# Sensor_Board.net
KiCad netlist of a schematic drawn in Altium Designer
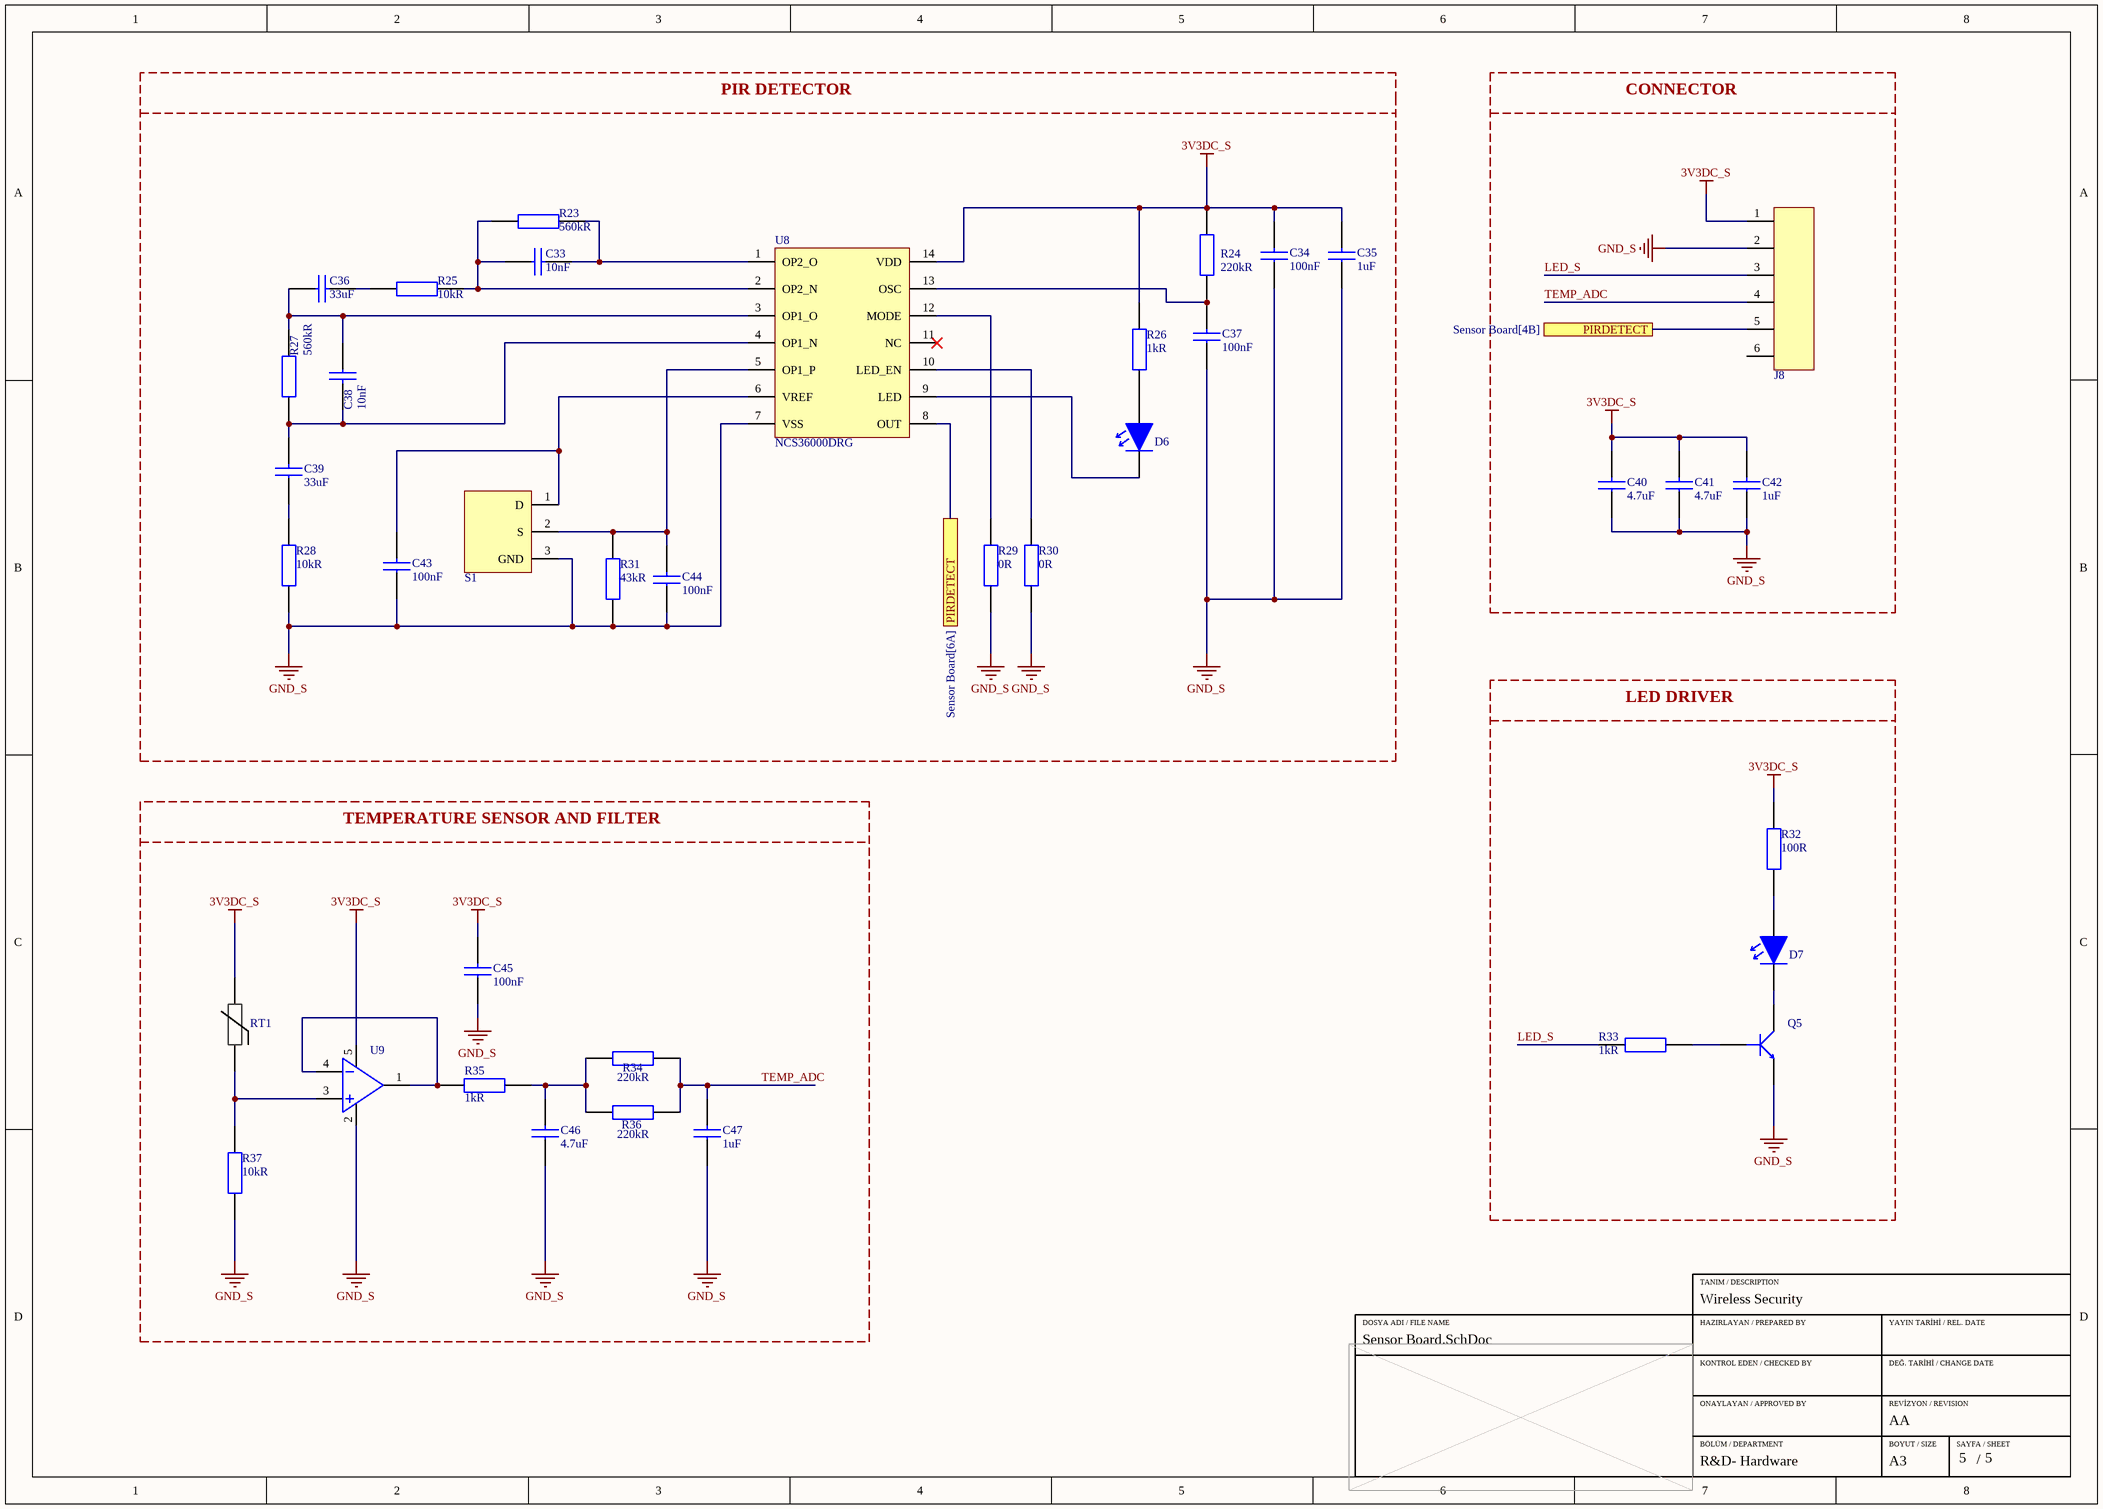
[diagram p0: Sensor Board.SchDoc]

(export (version "E")
  (design (tool "Eeschema 10.0.6"))
  (components
    (comp (ref "C33")
      (value "0603B103K160CT")
      (footprint "CAP_0603")
      (description "CAP CER 10nF %10 0603")
      (fields
        (field (name "MANUFACTURER") "Walsin Technologies")
        (field (name "TOLERANCE") "10%")
        (field (name "CAPACITANCE") "10nF")
        (field (name "DESIGNED BY") "Cem Uğurcan Özdemir")
      )
      (libsource (lib "UDEMY_Library") (part "CAP CER 10nF 0603"))
    )
    (comp (ref "C34")
      (value "C0603C104K5RACTU")
      (footprint "CAP_0603")
      (description "CAP CER 100nF %10 0603 SMD")
      (fields
        (field (name "MANUFACTURER") "KEMET")
        (field (name "TOLERANCE") "10%")
        (field (name "CAPACITANCE") "100nF")
        (field (name "DESIGNED BY") "Cem Uğurcan Özdemir")
      )
      (libsource (lib "UDEMY_Library") (part "CAP CER 100nF 0603"))
    )
    (comp (ref "C35")
      (value "CL21B105KBFNNNE")
      (footprint "CAP_0805")
      (description "CAP CER 1uF %10 0805")
      (fields
        (field (name "MANUFACTURER") "Samsung")
        (field (name "TOLERANCE") "10%")
        (field (name "CAPACITANCE") "1uF")
        (field (name "DESIGNED BY") "Cem Uğurcan Özdemir")
      )
      (libsource (lib "UDEMY_Library") (part "CAP CER 1uF 0805"))
    )
    (comp (ref "C36")
      (value "C3216X5R1E336M160AC")
      (footprint "CAP_1206")
      (description "CAP CER 33uF %20 1206 SMD")
      (fields
        (field (name "MANUFACTURER") "TDK")
        (field (name "TOLERANCE") "20%")
        (field (name "CAPACITANCE") "33uF")
        (field (name "DESIGNED BY") "Cem Uğurcan Özdemir")
      )
      (libsource (lib "UDEMY_Library") (part "CAP CER 33uF 1206"))
    )
    (comp (ref "C37")
      (value "C0603C104K5RACTU")
      (footprint "CAP_0603")
      (description "CAP CER 100nF %10 0603 SMD")
      (fields
        (field (name "MANUFACTURER") "KEMET")
        (field (name "TOLERANCE") "10%")
        (field (name "CAPACITANCE") "100nF")
        (field (name "DESIGNED BY") "Cem Uğurcan Özdemir")
      )
      (libsource (lib "UDEMY_Library") (part "CAP CER 100nF 0603"))
    )
    (comp (ref "C38")
      (value "0603B103K160CT")
      (footprint "CAP_0603")
      (description "CAP CER 10nF %10 0603")
      (fields
        (field (name "MANUFACTURER") "Walsin Technologies")
        (field (name "TOLERANCE") "10%")
        (field (name "CAPACITANCE") "10nF")
        (field (name "DESIGNED BY") "Cem Uğurcan Özdemir")
      )
      (libsource (lib "UDEMY_Library") (part "CAP CER 10nF 0603"))
    )
    (comp (ref "C39")
      (value "C3216X5R1E336M160AC")
      (footprint "CAP_1206")
      (description "CAP CER 33uF %20 1206 SMD")
      (fields
        (field (name "MANUFACTURER") "TDK")
        (field (name "TOLERANCE") "20%")
        (field (name "CAPACITANCE") "33uF")
        (field (name "DESIGNED BY") "Cem Uğurcan Özdemir")
      )
      (libsource (lib "UDEMY_Library") (part "CAP CER 33uF 1206"))
    )
    (comp (ref "C40")
      (value "CL21A475KAQNNNE")
      (footprint "CAP_0805")
      (description "CAP CER 4.7uF %10 0805")
      (fields
        (field (name "MANUFACTURER") "Samsung")
        (field (name "TOLERANCE") "10%")
        (field (name "CAPACITANCE") "4.7uF")
        (field (name "DESIGNED BY") "Cem Uğurcan Özdemir")
      )
      (libsource (lib "UDEMY_Library") (part "CAP CER 4.7uF 0805"))
    )
    (comp (ref "C41")
      (value "CL21A475KAQNNNE")
      (footprint "CAP_0805")
      (description "CAP CER 4.7uF %10 0805")
      (fields
        (field (name "MANUFACTURER") "Samsung")
        (field (name "TOLERANCE") "10%")
        (field (name "CAPACITANCE") "4.7uF")
        (field (name "DESIGNED BY") "Cem Uğurcan Özdemir")
      )
      (libsource (lib "UDEMY_Library") (part "CAP CER 4.7uF 0805"))
    )
    (comp (ref "C42")
      (value "CL21B105KBFNNNE")
      (footprint "CAP_0805")
      (description "CAP CER 1uF %10 0805")
      (fields
        (field (name "MANUFACTURER") "Samsung")
        (field (name "TOLERANCE") "10%")
        (field (name "CAPACITANCE") "1uF")
        (field (name "DESIGNED BY") "Cem Uğurcan Özdemir")
      )
      (libsource (lib "UDEMY_Library") (part "CAP CER 1uF 0805"))
    )
    (comp (ref "C43")
      (value "C0603C104K5RACTU")
      (footprint "CAP_0603")
      (description "CAP CER 100nF %10 0603 SMD")
      (fields
        (field (name "MANUFACTURER") "KEMET")
        (field (name "TOLERANCE") "10%")
        (field (name "CAPACITANCE") "100nF")
        (field (name "DESIGNED BY") "Cem Uğurcan Özdemir")
      )
      (libsource (lib "UDEMY_Library") (part "CAP CER 100nF 0603"))
    )
    (comp (ref "C44")
      (value "C0603C104K5RACTU")
      (footprint "CAP_0603")
      (description "CAP CER 100nF %10 0603 SMD")
      (fields
        (field (name "MANUFACTURER") "KEMET")
        (field (name "TOLERANCE") "10%")
        (field (name "CAPACITANCE") "100nF")
        (field (name "DESIGNED BY") "Cem Uğurcan Özdemir")
      )
      (libsource (lib "UDEMY_Library") (part "CAP CER 100nF 0603"))
    )
    (comp (ref "C45")
      (value "C0603C104K5RACTU")
      (footprint "CAP_0603")
      (description "CAP CER 100nF %10 0603 SMD")
      (fields
        (field (name "MANUFACTURER") "KEMET")
        (field (name "TOLERANCE") "10%")
        (field (name "CAPACITANCE") "100nF")
        (field (name "DESIGNED BY") "Cem Uğurcan Özdemir")
      )
      (libsource (lib "UDEMY_Library") (part "CAP CER 100nF 0603"))
    )
    (comp (ref "C46")
      (value "CL21A475KAQNNNE")
      (footprint "CAP_0805")
      (description "CAP CER 4.7uF %10 0805")
      (fields
        (field (name "MANUFACTURER") "Samsung")
        (field (name "TOLERANCE") "10%")
        (field (name "CAPACITANCE") "4.7uF")
        (field (name "DESIGNED BY") "Cem Uğurcan Özdemir")
      )
      (libsource (lib "UDEMY_Library") (part "CAP CER 4.7uF 0805"))
    )
    (comp (ref "C47")
      (value "CL21B105KBFNNNE")
      (footprint "CAP_0805")
      (description "CAP CER 1uF %10 0805")
      (fields
        (field (name "MANUFACTURER") "Samsung")
        (field (name "TOLERANCE") "10%")
        (field (name "CAPACITANCE") "1uF")
        (field (name "DESIGNED BY") "Cem Uğurcan Özdemir")
      )
      (libsource (lib "UDEMY_Library") (part "CAP CER 1uF 0805"))
    )
    (comp (ref "D6")
      (value "LTST-C171GKT")
      (footprint "LED_GREEN_0805")
      (description "Green 0805 130 º Min 5 mcd Typical 12 mcd Water Clear Lens SMT LED")
      (fields
        (field (name "MANUFACTURER") "Vishay Lite-On")
        (field (name "DESIGNED BY") "Cem Uğurcan Özdemir")
      )
      (libsource (lib "UDEMY_Library") (part "LED GREEN 0805"))
    )
    (comp (ref "D7")
      (value "LH R974-LP-1")
      (footprint "LED_RED_0805")
      (description "LED Uni-Color Hyper Red 660nm 2-Pin Chip 0805(2012Metric) T/R")
      (fields (field (name "MANUFACTURER") "Osram Opto") (field (name "DESIGNED BY") "Cem Uğurcan Özdemir"))
      (libsource (lib "UDEMY_Library") (part "LED RED 0805"))
    )
    (comp (ref "J8")
      (value "64800611622")
      (footprint "64800611622")
      (description "1.50mm 6PIN Connector")
      (fields
        (field (name "MANUFACTURER") "Wurth Electronics")
        (field (name "DESIGNED BY") "Cem Uğurcan Özdemir")
      )
      (libsource (lib "UDEMY_Library") (part "64800611622_conn_6pin"))
    )
    (comp (ref "Q5")
      (value "MMBT3904-7-F")
      (footprint "SOT-23F")
      (description "Transistor General Purpose BJT NPN 40 Volt 0.2A Automotive 3-Pin SOT-23")
      (fields (field (name "MANUFACTURER") "Diodes Zetex") (field (name "DESIGNED BY") "Cem Uğurcan Özdemir"))
      (libsource (lib "UDEMY_Library") (part "MMBT3904-7-F"))
    )
    (comp (ref "R23")
      (value "RC0603JR-07560KL")
      (footprint "RES_0603")
      (description "RES SMD 560K OHM 5% 1/10W 0603")
      (fields
        (field (name "MANUFACTURER") "Yageo")
        (field (name "TOLERANCE") "5%")
        (field (name "RESISTANCE") "560kR")
        (field (name "DESIGNED BY") "Cem Uğurcan Özdemir")
      )
      (libsource (lib "UDEMY_Library") (part "RES 560K OHM 0603"))
    )
    (comp (ref "R24")
      (value "RC0603JR-07220KL")
      (footprint "RES_0603")
      (description "RES 220K %5 OHM 0603 SMD")
      (fields
        (field (name "MANUFACTURER") "Yageo")
        (field (name "TOLERANCE") "5%")
        (field (name "RESISTANCE") "220kR")
        (field (name "DESIGNED BY") "Cem Uğurcan Özdemir")
      )
      (libsource (lib "") (part "RES 220K OHM 0603_1"))
    )
    (comp (ref "R25")
      (value "RC0603FR-0710KL")
      (footprint "RES_0603")
      (description "RES 10K %1 OHM 0603 SMD")
      (fields
        (field (name "MANUFACTURER") "Yageo")
        (field (name "TOLERANCE") "1%")
        (field (name "RESISTANCE") "10kR")
        (field (name "DESIGNED BY") "Cem Uğurcan Özdemir")
      )
      (libsource (lib "") (part "RES 10K OHM 0603_1"))
    )
    (comp (ref "R26")
      (value "RC0603FR-0710KL")
      (footprint "RES_0603")
      (description "RES 1K %1 OHM 0603 SMD")
      (fields
        (field (name "MANUFACTURER") "Yageo")
        (field (name "MANUFACTURER PART NUMBER") "RC0603JR-071KL")
        (field (name "RESISTANCE") "1kR")
        (field (name "DESIGNED BY") "Cem Uğurcan Özdemir")
      )
      (libsource (lib "UDEMY_Library") (part "RES 1K OHM 0603"))
    )
    (comp (ref "R27")
      (value "RC0603JR-07560KL")
      (footprint "RES_0603")
      (description "RES SMD 560K OHM 5% 1/10W 0603")
      (fields
        (field (name "MANUFACTURER") "Yageo")
        (field (name "TOLERANCE") "5%")
        (field (name "RESISTANCE") "560kR")
        (field (name "DESIGNED BY") "Cem Uğurcan Özdemir")
      )
      (libsource (lib "") (part "RES 560K OHM 0603_1"))
    )
    (comp (ref "R28")
      (value "RC0603FR-0710KL")
      (footprint "RES_0603")
      (description "RES 10K %1 OHM 0603 SMD")
      (fields
        (field (name "MANUFACTURER") "Yageo")
        (field (name "TOLERANCE") "1%")
        (field (name "RESISTANCE") "10kR")
        (field (name "DESIGNED BY") "Cem Uğurcan Özdemir")
      )
      (libsource (lib "UDEMY_Library") (part "RES 10K OHM 0603"))
    )
    (comp (ref "R29")
      (value "RC0603JR-070RL")
      (footprint "RES_0603")
      (description "RES 0 %1 OHM 0603 SMD")
      (fields
        (field (name "MANUFACTURER") "Yageo")
        (field (name "TOLERANCE") "1%")
        (field (name "RESISTANCE") "0R")
        (field (name "DESIGNED BY") "Cem Uğurcan Özdemir")
      )
      (libsource (lib "UDEMY_Library") (part "RES 0 OHM 0603"))
    )
    (comp (ref "R30")
      (value "RC0603JR-070RL")
      (footprint "RES_0603")
      (description "RES 0 %1 OHM 0603 SMD")
      (fields
        (field (name "MANUFACTURER") "Yageo")
        (field (name "TOLERANCE") "1%")
        (field (name "RESISTANCE") "0R")
        (field (name "DESIGNED BY") "Cem Uğurcan Özdemir")
      )
      (libsource (lib "UDEMY_Library") (part "RES 0 OHM 0603"))
    )
    (comp (ref "R31")
      (value "RC0603JR-0743KL")
      (footprint "RES_0603")
      (description "RES 43K %5 OHM 0603 SMD")
      (fields
        (field (name "MANUFACTURER") "Yageo")
        (field (name "TOLERANCE") "5%")
        (field (name "RESISTANCE") "43kR")
        (field (name "DESIGNED BY") "Cem Uğurcan Özdemir")
      )
      (libsource (lib "UDEMY_Library") (part "RES 43K OHM 0603"))
    )
    (comp (ref "R32")
      (value "RC0603JR-07100RL")
      (footprint "RES_0603")
      (description "RES 100 %5 OHM 0603 SMD")
      (fields
        (field (name "MANUFACTURER") "Yageo")
        (field (name "TOLERANCE") "5%")
        (field (name "RESISTANCE") "100R")
        (field (name "DESIGNED BY") "Cem Uğurcan Özdemir")
      )
      (libsource (lib "UDEMY_Library") (part "RES 100 OHM 0603"))
    )
    (comp (ref "R33")
      (value "RC0603FR-0710KL")
      (footprint "RES_0603")
      (description "RES 1K %1 OHM 0603 SMD")
      (fields
        (field (name "MANUFACTURER") "Yageo")
        (field (name "MANUFACTURER PART NUMBER") "RC0603JR-071KL")
        (field (name "RESISTANCE") "1kR")
        (field (name "DESIGNED BY") "Cem Uğurcan Özdemir")
      )
      (libsource (lib "") (part "RES 1K OHM 0603_1"))
    )
    (comp (ref "R34")
      (value "RC0603JR-07220KL")
      (footprint "RES_0603")
      (description "RES 220K %5 OHM 0603 SMD")
      (fields
        (field (name "MANUFACTURER") "Yageo")
        (field (name "TOLERANCE") "5%")
        (field (name "RESISTANCE") "220kR")
        (field (name "DESIGNED BY") "Cem Uğurcan Özdemir")
      )
      (libsource (lib "UDEMY_Library") (part "RES 220K OHM 0603"))
    )
    (comp (ref "R35")
      (value "RC0603FR-0710KL")
      (footprint "RES_0603")
      (description "RES 1K %1 OHM 0603 SMD")
      (fields
        (field (name "MANUFACTURER") "Yageo")
        (field (name "MANUFACTURER PART NUMBER") "RC0603JR-071KL")
        (field (name "RESISTANCE") "1kR")
        (field (name "DESIGNED BY") "Cem Uğurcan Özdemir")
      )
      (libsource (lib "") (part "RES 1K OHM 0603_1"))
    )
    (comp (ref "R36")
      (value "RC0603JR-07220KL")
      (footprint "RES_0603")
      (description "RES 220K %5 OHM 0603 SMD")
      (fields
        (field (name "MANUFACTURER") "Yageo")
        (field (name "TOLERANCE") "5%")
        (field (name "RESISTANCE") "220kR")
        (field (name "DESIGNED BY") "Cem Uğurcan Özdemir")
      )
      (libsource (lib "UDEMY_Library") (part "RES 220K OHM 0603"))
    )
    (comp (ref "R37")
      (value "RC0603FR-0710KL")
      (footprint "RES_0603")
      (description "RES 10K %1 OHM 0603 SMD")
      (fields
        (field (name "MANUFACTURER") "Yageo")
        (field (name "TOLERANCE") "1%")
        (field (name "RESISTANCE") "10kR")
        (field (name "DESIGNED BY") "Cem Uğurcan Özdemir")
      )
      (libsource (lib "UDEMY_Library") (part "RES 10K OHM 0603"))
    )
    (comp (ref "RT1")
      (value "TFPT1206L1002FM")
      (footprint "RES_1206")
      (description "Thermistor PTC 10K Ohm 1% 1206")
      (fields
        (field (name "MANUFACTURER") "Vishay Dale")
        (field (name "TOLERANCE") "1%")
        (field (name "DESIGNED BY") "Cem Uğurcan Özdemir")
      )
      (libsource (lib "UDEMY_Library") (part "TFPT1206L1002FM"))
    )
    (comp (ref "S1")
      (value "LHI 878/3902")
      (footprint "LHI 878")
      (description "SENSOR PYRO DETECTOR DUAL MOTION")
      (fields (field (name "DESIGNED BY") "Cem Uğurcan Özdemir"))
      (libsource (lib "UDEMY_Library") (part "LHI 878/3902"))
    )
    (comp (ref "U8")
      (value "NCS36000DRG")
      (footprint "SOIC14")
      (description "PIR Controller Low Noise Amplifiers and LDO Regulator 14-Pin SOIC N T/R")
      (fields
        (field (name "MANUFACTURER") "ON Semiconductor")
        (field (name "DESIGNED BY") "Cem Uğurcan Özdemir")
      )
      (libsource (lib "UDEMY_Library") (part "NCS36000"))
    )
    (comp (ref "U9")
      (value "OPA314AIDBVR")
      (footprint "SOT23-5")
      (description "Op Amp OPA314")
      (fields
        (field (name "MANUFACTURER") "Texas Instruments")
        (field (name "DESIGNED BY") "Cem Uğurcan Özdemir")
      )
      (libsource (lib "UDEMY_Library") (part "OPA314"))
    )
  )
  (nets
    (net (code "1") (name "/LED_S") (class "Default")
      (node (ref "J8") (pin "3") (pintype "power_in"))
      (node (ref "R33") (pin "1") (pinfunction "1_1") (pintype "passive"))
    )
    (net (code "2") (name "/PIRDETECT") (class "Default")
      (node (ref "J8") (pin "5") (pintype "power_in"))
      (node (ref "U8") (pin "8") (pinfunction "OUT_8") (pintype "passive"))
    )
    (net (code "3") (name "/TEMP_ADC") (class "Default")
      (node (ref "C47") (pin "2") (pinfunction "2_2") (pintype "passive"))
      (node (ref "J8") (pin "4") (pintype "power_in"))
      (node (ref "R34") (pin "2") (pinfunction "2_2") (pintype "passive"))
      (node (ref "R36") (pin "2") (pinfunction "2_2") (pintype "passive"))
    )
    (net (code "4") (name "3V3DC_S") (class "Default")
      (node (ref "C34") (pin "2") (pinfunction "2_2") (pintype "passive"))
      (node (ref "C35") (pin "2") (pinfunction "2_2") (pintype "passive"))
      (node (ref "C40") (pin "2") (pinfunction "2_2") (pintype "passive"))
      (node (ref "C41") (pin "2") (pinfunction "2_2") (pintype "passive"))
      (node (ref "C42") (pin "2") (pinfunction "2_2") (pintype "passive"))
      (node (ref "C45") (pin "2") (pinfunction "2_2") (pintype "passive"))
      (node (ref "J8") (pin "1") (pintype "power_in"))
      (node (ref "R24") (pin "2") (pinfunction "2_2") (pintype "passive"))
      (node (ref "R26") (pin "2") (pinfunction "2_2") (pintype "passive"))
      (node (ref "R32") (pin "2") (pinfunction "2_2") (pintype "passive"))
      (node (ref "RT1") (pin "2") (pinfunction "2_2") (pintype "passive"))
      (node (ref "U8") (pin "14") (pinfunction "VDD_14") (pintype "passive"))
      (node (ref "U9") (pin "5") (pinfunction "5_5") (pintype "passive"))
    )
    (net (code "5") (name "GND_S") (class "Default")
      (node (ref "C34") (pin "1") (pinfunction "1_1") (pintype "passive"))
      (node (ref "C35") (pin "1") (pinfunction "1_1") (pintype "passive"))
      (node (ref "C37") (pin "1") (pinfunction "1_1") (pintype "passive"))
      (node (ref "C40") (pin "1") (pinfunction "1_1") (pintype "passive"))
      (node (ref "C41") (pin "1") (pinfunction "1_1") (pintype "passive"))
      (node (ref "C42") (pin "1") (pinfunction "1_1") (pintype "passive"))
      (node (ref "C43") (pin "1") (pinfunction "1_1") (pintype "passive"))
      (node (ref "C44") (pin "1") (pinfunction "1_1") (pintype "passive"))
      (node (ref "C45") (pin "1") (pinfunction "1_1") (pintype "passive"))
      (node (ref "C46") (pin "1") (pinfunction "1_1") (pintype "passive"))
      (node (ref "C47") (pin "1") (pinfunction "1_1") (pintype "passive"))
      (node (ref "J8") (pin "2") (pintype "power_in"))
      (node (ref "Q5") (pin "2") (pinfunction "E_2") (pintype "power_in"))
      (node (ref "R28") (pin "1") (pinfunction "1_1") (pintype "passive"))
      (node (ref "R29") (pin "1") (pinfunction "1_1") (pintype "passive"))
      (node (ref "R30") (pin "1") (pinfunction "1_1") (pintype "passive"))
      (node (ref "R31") (pin "1") (pinfunction "1_1") (pintype "passive"))
      (node (ref "R37") (pin "1") (pinfunction "1_1") (pintype "passive"))
      (node (ref "S1") (pin "3") (pinfunction "GND_3") (pintype "passive"))
      (node (ref "U8") (pin "7") (pinfunction "VSS_7") (pintype "passive"))
      (node (ref "U9") (pin "2") (pinfunction "2_2") (pintype "passive"))
    )
    (net (code "6") (name "Net-(C36-Pad2)") (class "Default")
      (node (ref "C36") (pin "2") (pinfunction "2_2") (pintype "passive"))
      (node (ref "R25") (pin "1") (pinfunction "1_1") (pintype "passive"))
    )
    (net (code "7") (name "Net-(C39-Pad1)") (class "Default")
      (node (ref "C39") (pin "1") (pinfunction "1_1") (pintype "passive"))
      (node (ref "R28") (pin "2") (pinfunction "2_2") (pintype "passive"))
    )
    (net (code "8") (name "Net-(C46-Pad2)") (class "Default")
      (node (ref "C46") (pin "2") (pinfunction "2_2") (pintype "passive"))
      (node (ref "R34") (pin "1") (pinfunction "1_1") (pintype "passive"))
      (node (ref "R35") (pin "2") (pinfunction "2_2") (pintype "passive"))
      (node (ref "R36") (pin "1") (pinfunction "1_1") (pintype "passive"))
    )
    (net (code "9") (name "Net-(D6-Pad2)") (class "Default")
      (node (ref "D6") (pin "2") (pinfunction "2_2") (pintype "power_in"))
      (node (ref "R26") (pin "1") (pinfunction "1_1") (pintype "passive"))
    )
    (net (code "10") (name "Net-(D7-Pad2)") (class "Default")
      (node (ref "D7") (pin "2") (pinfunction "2_2") (pintype "power_in"))
      (node (ref "R32") (pin "1") (pinfunction "1_1") (pintype "passive"))
    )
    (net (code "11") (name "Net-(Q5-B)") (class "Default")
      (node (ref "Q5") (pin "1") (pinfunction "B_1") (pintype "power_in"))
      (node (ref "R33") (pin "2") (pinfunction "2_2") (pintype "passive"))
    )
    (net (code "12") (name "Net-(Q5-C)") (class "Default")
      (node (ref "D7") (pin "1") (pinfunction "1_1") (pintype "power_in"))
      (node (ref "Q5") (pin "3") (pinfunction "C_3") (pintype "power_in"))
    )
    (net (code "13") (name "Net-(R35-Pad1)") (class "Default")
      (node (ref "R35") (pin "1") (pinfunction "1_1") (pintype "passive"))
      (node (ref "U9") (pin "1") (pinfunction "1_1") (pintype "passive"))
      (node (ref "U9") (pin "4") (pinfunction "4_4") (pintype "passive"))
    )
    (net (code "14") (name "Net-(R37-Pad2)") (class "Default")
      (node (ref "R37") (pin "2") (pinfunction "2_2") (pintype "passive"))
      (node (ref "RT1") (pin "1") (pinfunction "1_1") (pintype "passive"))
      (node (ref "U9") (pin "3") (pinfunction "3_3") (pintype "passive"))
    )
    (net (code "15") (name "Net-(S1-D)") (class "Default")
      (node (ref "C43") (pin "2") (pinfunction "2_2") (pintype "passive"))
      (node (ref "S1") (pin "1") (pinfunction "D_1") (pintype "passive"))
      (node (ref "U8") (pin "6") (pinfunction "VREF_6") (pintype "passive"))
    )
    (net (code "16") (name "Net-(S1-S)") (class "Default")
      (node (ref "C44") (pin "2") (pinfunction "2_2") (pintype "passive"))
      (node (ref "R31") (pin "2") (pinfunction "2_2") (pintype "passive"))
      (node (ref "S1") (pin "2") (pinfunction "S_2") (pintype "passive"))
      (node (ref "U8") (pin "5") (pinfunction "OP1_P_5") (pintype "passive"))
    )
    (net (code "17") (name "Net-(U8-LED)") (class "Default")
      (node (ref "D6") (pin "1") (pinfunction "1_1") (pintype "power_in"))
      (node (ref "U8") (pin "9") (pinfunction "LED_9") (pintype "passive"))
    )
    (net (code "18") (name "Net-(U8-LED_EN)") (class "Default")
      (node (ref "R30") (pin "2") (pinfunction "2_2") (pintype "passive"))
      (node (ref "U8") (pin "10") (pinfunction "LED_EN_10") (pintype "passive"))
    )
    (net (code "19") (name "Net-(U8-MODE)") (class "Default")
      (node (ref "R29") (pin "2") (pinfunction "2_2") (pintype "passive"))
      (node (ref "U8") (pin "12") (pinfunction "MODE_12") (pintype "passive"))
    )
    (net (code "20") (name "Net-(U8-OP1_N)") (class "Default")
      (node (ref "C38") (pin "2") (pinfunction "2_2") (pintype "passive"))
      (node (ref "C39") (pin "2") (pinfunction "2_2") (pintype "passive"))
      (node (ref "R27") (pin "1") (pinfunction "1_1") (pintype "passive"))
      (node (ref "U8") (pin "4") (pinfunction "OP1_N_4") (pintype "passive"))
    )
    (net (code "21") (name "Net-(U8-OP1_O)") (class "Default")
      (node (ref "C36") (pin "1") (pinfunction "1_1") (pintype "passive"))
      (node (ref "C38") (pin "1") (pinfunction "1_1") (pintype "passive"))
      (node (ref "R27") (pin "2") (pinfunction "2_2") (pintype "passive"))
      (node (ref "U8") (pin "3") (pinfunction "OP1_O_3") (pintype "passive"))
    )
    (net (code "22") (name "Net-(U8-OP2_N)") (class "Default")
      (node (ref "C33") (pin "1") (pinfunction "1_1") (pintype "passive"))
      (node (ref "R23") (pin "1") (pinfunction "1_1") (pintype "passive"))
      (node (ref "R25") (pin "2") (pinfunction "2_2") (pintype "passive"))
      (node (ref "U8") (pin "2") (pinfunction "OP2_N_2") (pintype "passive"))
    )
    (net (code "23") (name "Net-(U8-OP2_O)") (class "Default")
      (node (ref "C33") (pin "2") (pinfunction "2_2") (pintype "passive"))
      (node (ref "R23") (pin "2") (pinfunction "2_2") (pintype "passive"))
      (node (ref "U8") (pin "1") (pinfunction "OP2_O_1") (pintype "passive"))
    )
    (net (code "24") (name "Net-(U8-OSC)") (class "Default")
      (node (ref "C37") (pin "2") (pinfunction "2_2") (pintype "passive"))
      (node (ref "R24") (pin "1") (pinfunction "1_1") (pintype "passive"))
      (node (ref "U8") (pin "13") (pinfunction "OSC_13") (pintype "passive"))
    )
    (net (code "25") (name "unconnected-(J8-Pad6)") (class "Default")
      (node (ref "J8") (pin "6") (pintype "power_in"))
    )
    (net (code "26") (name "unconnected-(U8-NC-Pad11)") (class "Default")
      (node (ref "U8") (pin "11") (pinfunction "NC_11") (pintype "passive+no_connect"))
    )
  )
)
